# GPS_Sheet.net
KiCad netlist of a schematic drawn in Altium Designer
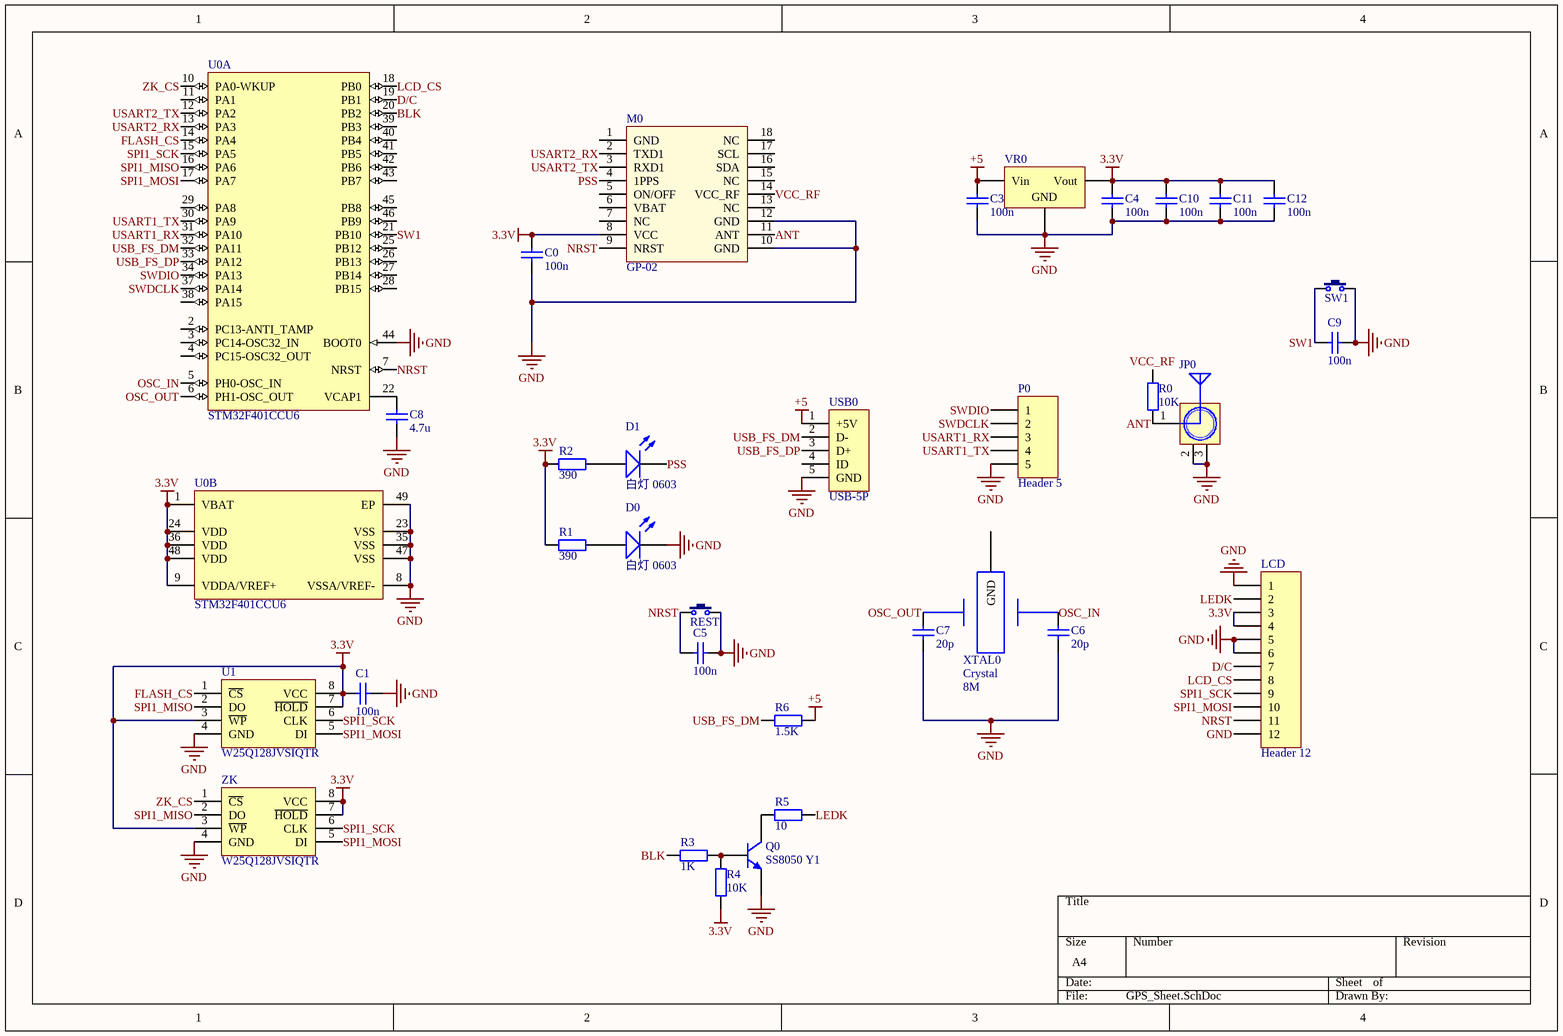
[diagram p0: GPS_Sheet.SchDoc]

(export (version "E")
  (design (tool "Eeschema 10.0.6"))
  (components
    (comp (ref "C0")
      (value "100n")
      (footprint "0805_C")
      (description "贴片电容")
      (libsource (lib "Miscellaneous Devices LC") (part "0805 100nF(104) 10% 50V"))
    )
    (comp (ref "C1")
      (value "100n")
      (footprint "0805_C")
      (description "贴片电容")
      (libsource (lib "Miscellaneous Devices LC") (part "0805 100nF(104) 10% 50V"))
    )
    (comp (ref "C3")
      (value "100n")
      (footprint "0805_C")
      (description "贴片电容")
      (libsource (lib "Miscellaneous Devices LC") (part "0805 100nF(104) 10% 50V"))
    )
    (comp (ref "C4")
      (value "100n")
      (footprint "0805_C")
      (description "贴片电容")
      (libsource (lib "Miscellaneous Devices LC") (part "0805 100nF(104) 10% 50V"))
    )
    (comp (ref "C5")
      (value "100n")
      (footprint "0805_C")
      (description "贴片电容")
      (libsource (lib "Miscellaneous Devices LC") (part "0805 100nF(104) 10% 50V"))
    )
    (comp (ref "C6")
      (value "20p")
      (footprint "0805_C")
      (description "贴片电容")
      (libsource (lib "Miscellaneous Devices LC") (part "0805 20pF (200) 5% 50V"))
    )
    (comp (ref "C7")
      (value "20p")
      (footprint "0805_C")
      (description "贴片电容")
      (libsource (lib "Miscellaneous Devices LC") (part "0805 20pF (200) 5% 50V"))
    )
    (comp (ref "C8")
      (value "4.7u")
      (footprint "0805_C")
      (description "贴片电容")
      (libsource (lib "Miscellaneous Devices LC") (part "0805 4.7uF (475) 10% 25V"))
    )
    (comp (ref "C9")
      (value "100n")
      (footprint "0805_C")
      (description "贴片电容")
      (libsource (lib "Miscellaneous Devices LC") (part "0805 100nF(104) 10% 50V"))
    )
    (comp (ref "C10")
      (value "100n")
      (footprint "0805_C")
      (description "贴片电容")
      (libsource (lib "Miscellaneous Devices LC") (part "0805 100nF(104) 10% 50V"))
    )
    (comp (ref "C11")
      (value "100n")
      (footprint "0805_C")
      (description "贴片电容")
      (libsource (lib "Miscellaneous Devices LC") (part "0805 100nF(104) 10% 50V"))
    )
    (comp (ref "C12")
      (value "100n")
      (footprint "0805_C")
      (description "贴片电容")
      (libsource (lib "Miscellaneous Devices LC") (part "0805 100nF(104) 10% 50V"))
    )
    (comp (ref "D0")
      (value "白灯 0603")
      (footprint "0603_LED_S1")
      (description "发光二极管")
      (libsource (lib "Miscellaneous Devices LC") (part "0603 白灯"))
    )
    (comp (ref "D1")
      (value "白灯 0603")
      (footprint "0603_LED_S1")
      (description "发光二极管")
      (libsource (lib "Miscellaneous Devices LC") (part "0603 白灯"))
    )
    (comp (ref "JP0")
      (value "SMA")
      (footprint "IPX")
      (description "SMA-2.4G射频天线接口")
      (fields (field (name "版权归属") "源创客"))
      (libsource (lib "接口类") (part "SMA"))
    )
    (comp (ref "LCD")
      (value "Header 12")
      (footprint "1.3_inch_LCD")
      (description "Header, 12-Pin")
      (fields (field (name "PUBLISHER") "Altium Limited"))
      (libsource (lib "Miscellaneous Connectors") (part "Header 12"))
    )
    (comp (ref "M0") (value "GP-02") (footprint "GP-02") (libsource (lib "GP-02 SCHLIB") (part "GP-02")))
    (comp (ref "P0")
      (value "Header 5")
      (footprint "HDR1X5")
      (description "Header, 5-Pin")
      (fields (field (name "PUBLISHER") "Altium Limited"))
      (libsource (lib "Miscellaneous Connectors") (part "Header 5"))
    )
    (comp (ref "Q0")
      (value "SS8050 Y1")
      (footprint "SOT-23(SOT-23-3)")
      (description "三极管")
      (libsource (lib "Miscellaneous Devices LC") (part "SOT-23 SS8050 Y1"))
    )
    (comp (ref "R0")
      (value "10K")
      (footprint "0805_R")
      (description "贴片电阻")
      (libsource (lib "Miscellaneous Devices LC") (part "0805 10KΩ (1002) 1%"))
    )
    (comp (ref "R1")
      (value "390")
      (footprint "0805_R")
      (description "贴片电阻")
      (libsource (lib "Miscellaneous Devices LC") (part "0805 390Ω (3900) 1%"))
    )
    (comp (ref "R2")
      (value "390")
      (footprint "0805_R")
      (description "贴片电阻")
      (libsource (lib "Miscellaneous Devices LC") (part "0805 390Ω (3900) 1%"))
    )
    (comp (ref "R3")
      (value "1K")
      (footprint "0805_R")
      (description "贴片电阻")
      (libsource (lib "Miscellaneous Devices LC") (part "0805 1KΩ (1001) 1%"))
    )
    (comp (ref "R4")
      (value "10K")
      (footprint "0805_R")
      (description "贴片电阻")
      (libsource (lib "Miscellaneous Devices LC") (part "0805 10KΩ (1002) 1%"))
    )
    (comp (ref "R5")
      (value "10")
      (footprint "0805_R")
      (description "贴片电阻")
      (libsource (lib "Miscellaneous Devices LC") (part "0805 10Ω (10R0) 1%"))
    )
    (comp (ref "R6")
      (value "1.5K")
      (footprint "0805_R")
      (description "贴片电阻")
      (libsource (lib "Miscellaneous Devices LC") (part "0805 1.5KΩ (1501) 1%"))
    )
    (comp (ref "REST")
      (value "3x6x5")
      (footprint "TSW SMD-3*6*2.5")
      (description "3x6轻触开关")
      (fields (field (name "版权归属") "源创客"))
      (libsource (lib "按键-开关") (part "TSW 3x6"))
    )
    (comp (ref "SW1")
      (value "3x6x5")
      (footprint "TSW SMD-3*6*2.5")
      (description "3x6轻触开关")
      (fields (field (name "版权归属") "源创客"))
      (libsource (lib "按键-开关") (part "TSW 3x6"))
    )
    (comp (ref "U0")
      (value "STM32F401CCU6")
      (footprint "STM-UFQFPN48_N")
      (fields (field (name "MANUFACTURER") "STMicroelectronics"))
      (libsource (lib "STMicroelectronics STM32 F4") (part "STM32F401CCU6"))
    )
    (comp (ref "U1")
      (value "W25Q128JVSIQTR")
      (footprint "SOIC-8_208mil")
      (description "Flash ROM")
      (libsource (lib "Miscellaneous Devices LC") (part "W25Q128JVSIQTR_[C97521]"))
    )
    (comp (ref "USB0")
      (value "USB-5P")
      (footprint "USB-MICRO_B")
      (description "微型USB母座")
      (fields (field (name "版权归属") "源创客"))
      (libsource (lib "接口类") (part "USB-5P"))
    )
    (comp (ref "VR0")
      (value "AMS1117-3.3")
      (footprint "SOT-223")
      (description "低压差线性稳压(LDO)")
      (libsource (lib "Miscellaneous Devices LC") (part "SOT-223 AMS1117-3.3"))
    )
    (comp (ref "XTAL0")
      (value "Crystal")
      (footprint "XTAL_DIP")
      (description "Crystal without source")
      (fields (field (name "FREQUENCE") "8M"))
      (libsource (lib "SmallJu_Lib") (part "XTAL"))
    )
    (comp (ref "ZK")
      (value "W25Q128JVSIQTR")
      (footprint "SOIC-8_208mil")
      (description "Flash ROM")
      (libsource (lib "Miscellaneous Devices LC") (part "W25Q128JVSIQTR_[C97521]"))
    )
  )
  (nets
    (net (code "1") (name "+5") (class "Default")
      (node (ref "C3") (pin "2") (pinfunction "2_2") (pintype "passive"))
      (node (ref "R6") (pin "2") (pinfunction "2_2") (pintype "passive"))
      (node (ref "USB0") (pin "1") (pinfunction "+5V_1") (pintype "passive"))
      (node (ref "VR0") (pin "3") (pinfunction "Vin_3") (pintype "passive"))
    )
    (net (code "2") (name "/ANT") (class "Default")
      (node (ref "JP0") (pin "1") (pinfunction "ANT_1") (pintype "passive"))
      (node (ref "M0") (pin "11") (pinfunction "ANT_11") (pintype "passive"))
      (node (ref "R0") (pin "1") (pinfunction "1_1") (pintype "passive"))
    )
    (net (code "3") (name "/BLK") (class "Default")
      (node (ref "R3") (pin "2") (pinfunction "2_2") (pintype "passive"))
      (node (ref "U0") (pin "20") (pinfunction "PB2_20") (pintype "bidirectional"))
    )
    (net (code "4") (name "/D{slash}C") (class "Default")
      (node (ref "LCD") (pin "7") (pinfunction "7_7") (pintype "passive"))
      (node (ref "U0") (pin "19") (pinfunction "PB1_19") (pintype "bidirectional"))
    )
    (net (code "5") (name "/FLASH_CS") (class "Default")
      (node (ref "U0") (pin "14") (pinfunction "PA4_14") (pintype "bidirectional"))
      (node (ref "U1") (pin "1") (pinfunction "~{CS}_1") (pintype "passive"))
    )
    (net (code "6") (name "/LCD_CS") (class "Default")
      (node (ref "LCD") (pin "8") (pinfunction "8_8") (pintype "passive"))
      (node (ref "U0") (pin "18") (pinfunction "PB0_18") (pintype "bidirectional"))
    )
    (net (code "7") (name "/LEDK") (class "Default")
      (node (ref "LCD") (pin "2") (pinfunction "2_2") (pintype "passive"))
      (node (ref "R5") (pin "2") (pinfunction "2_2") (pintype "passive"))
    )
    (net (code "8") (name "/NRST") (class "Default")
      (node (ref "C5") (pin "1") (pinfunction "1_1") (pintype "passive"))
      (node (ref "LCD") (pin "11") (pinfunction "11_11") (pintype "passive"))
      (node (ref "M0") (pin "9") (pinfunction "NRST_9") (pintype "passive"))
      (node (ref "REST") (pin "1") (pinfunction "1_1") (pintype "passive"))
      (node (ref "U0") (pin "7") (pinfunction "NRST_7") (pintype "bidirectional"))
    )
    (net (code "9") (name "/OSC_IN") (class "Default")
      (node (ref "C6") (pin "2") (pinfunction "2_2") (pintype "passive"))
      (node (ref "U0") (pin "5") (pinfunction "PH0-OSC_IN_5") (pintype "bidirectional"))
      (node (ref "XTAL0") (pin "1") (pintype "passive"))
    )
    (net (code "10") (name "/OSC_OUT") (class "Default")
      (node (ref "C7") (pin "2") (pinfunction "2_2") (pintype "passive"))
      (node (ref "U0") (pin "6") (pinfunction "PH1-OSC_OUT_6") (pintype "bidirectional"))
      (node (ref "XTAL0") (pin "2") (pintype "passive"))
    )
    (net (code "11") (name "/PSS") (class "Default")
      (node (ref "D1") (pin "K") (pinfunction "K_K") (pintype "passive"))
      (node (ref "M0") (pin "4") (pinfunction "1PPS_4") (pintype "passive"))
    )
    (net (code "12") (name "/SPI1_MISO") (class "Default")
      (node (ref "U0") (pin "16") (pinfunction "PA6_16") (pintype "bidirectional"))
      (node (ref "U1") (pin "2") (pinfunction "DO_2") (pintype "passive"))
      (node (ref "ZK") (pin "2") (pinfunction "DO_2") (pintype "passive"))
    )
    (net (code "13") (name "/SPI1_MOSI") (class "Default")
      (node (ref "LCD") (pin "10") (pinfunction "10_10") (pintype "passive"))
      (node (ref "U0") (pin "17") (pinfunction "PA7_17") (pintype "bidirectional"))
      (node (ref "U1") (pin "5") (pinfunction "DI_5") (pintype "passive"))
      (node (ref "ZK") (pin "5") (pinfunction "DI_5") (pintype "passive"))
    )
    (net (code "14") (name "/SPI1_SCK") (class "Default")
      (node (ref "LCD") (pin "9") (pinfunction "9_9") (pintype "passive"))
      (node (ref "U0") (pin "15") (pinfunction "PA5_15") (pintype "bidirectional"))
      (node (ref "U1") (pin "6") (pinfunction "CLK_6") (pintype "passive"))
      (node (ref "ZK") (pin "6") (pinfunction "CLK_6") (pintype "passive"))
    )
    (net (code "15") (name "/SW1") (class "Default")
      (node (ref "C9") (pin "1") (pinfunction "1_1") (pintype "passive"))
      (node (ref "SW1") (pin "1") (pinfunction "1_1") (pintype "passive"))
      (node (ref "U0") (pin "21") (pinfunction "PB10_21") (pintype "bidirectional"))
    )
    (net (code "16") (name "/SWDCLK") (class "Default")
      (node (ref "P0") (pin "2") (pinfunction "2_2") (pintype "passive"))
      (node (ref "U0") (pin "37") (pinfunction "PA14_37") (pintype "bidirectional"))
    )
    (net (code "17") (name "/SWDIO") (class "Default")
      (node (ref "P0") (pin "1") (pinfunction "1_1") (pintype "passive"))
      (node (ref "U0") (pin "34") (pinfunction "PA13_34") (pintype "bidirectional"))
    )
    (net (code "18") (name "/USART1_RX") (class "Default")
      (node (ref "P0") (pin "3") (pinfunction "3_3") (pintype "passive"))
      (node (ref "U0") (pin "31") (pinfunction "PA10_31") (pintype "bidirectional"))
    )
    (net (code "19") (name "/USART1_TX") (class "Default")
      (node (ref "P0") (pin "4") (pinfunction "4_4") (pintype "passive"))
      (node (ref "U0") (pin "30") (pinfunction "PA9_30") (pintype "bidirectional"))
    )
    (net (code "20") (name "/USART2_RX") (class "Default")
      (node (ref "M0") (pin "2") (pinfunction "TXD1_2") (pintype "passive"))
      (node (ref "U0") (pin "13") (pinfunction "PA3_13") (pintype "bidirectional"))
    )
    (net (code "21") (name "/USART2_TX") (class "Default")
      (node (ref "M0") (pin "3") (pinfunction "RXD1_3") (pintype "passive"))
      (node (ref "U0") (pin "12") (pinfunction "PA2_12") (pintype "bidirectional"))
    )
    (net (code "22") (name "/USB_FS_DM") (class "Default")
      (node (ref "R6") (pin "1") (pinfunction "1_1") (pintype "passive"))
      (node (ref "U0") (pin "32") (pinfunction "PA11_32") (pintype "bidirectional"))
      (node (ref "USB0") (pin "2") (pinfunction "D-_2") (pintype "passive"))
    )
    (net (code "23") (name "/USB_FS_DP") (class "Default")
      (node (ref "U0") (pin "33") (pinfunction "PA12_33") (pintype "bidirectional"))
      (node (ref "USB0") (pin "3") (pinfunction "D+_3") (pintype "passive"))
    )
    (net (code "24") (name "/VCC_RF") (class "Default")
      (node (ref "M0") (pin "14") (pinfunction "VCC_RF_14") (pintype "passive"))
      (node (ref "R0") (pin "2") (pinfunction "2_2") (pintype "passive"))
    )
    (net (code "25") (name "/ZK_CS") (class "Default")
      (node (ref "U0") (pin "10") (pinfunction "PA0-WKUP_10") (pintype "bidirectional"))
      (node (ref "ZK") (pin "1") (pinfunction "~{CS}_1") (pintype "passive"))
    )
    (net (code "26") (name "3.3V") (class "Default")
      (node (ref "C0") (pin "2") (pinfunction "2_2") (pintype "passive"))
      (node (ref "C1") (pin "2") (pinfunction "2_2") (pintype "passive"))
      (node (ref "C10") (pin "2") (pinfunction "2_2") (pintype "passive"))
      (node (ref "C11") (pin "2") (pinfunction "2_2") (pintype "passive"))
      (node (ref "C12") (pin "2") (pinfunction "2_2") (pintype "passive"))
      (node (ref "C4") (pin "2") (pinfunction "2_2") (pintype "passive"))
      (node (ref "LCD") (pin "3") (pinfunction "3_3") (pintype "passive"))
      (node (ref "LCD") (pin "4") (pinfunction "4_4") (pintype "passive"))
      (node (ref "M0") (pin "8") (pinfunction "VCC_8") (pintype "passive"))
      (node (ref "R1") (pin "1") (pinfunction "1_1") (pintype "passive"))
      (node (ref "R2") (pin "1") (pinfunction "1_1") (pintype "passive"))
      (node (ref "R4") (pin "1") (pinfunction "1_1") (pintype "passive"))
      (node (ref "U0") (pin "1") (pinfunction "VBAT_1") (pintype "power_in"))
      (node (ref "U0") (pin "24") (pinfunction "VDD_24") (pintype "power_in"))
      (node (ref "U0") (pin "36") (pinfunction "VDD_36") (pintype "power_in"))
      (node (ref "U0") (pin "48") (pinfunction "VDD_48") (pintype "power_in"))
      (node (ref "U0") (pin "9") (pinfunction "VDDA/VREF+_9") (pintype "power_in"))
      (node (ref "U1") (pin "3") (pinfunction "~{WP}_3") (pintype "passive"))
      (node (ref "U1") (pin "7") (pinfunction "~{HOLD}_7") (pintype "passive"))
      (node (ref "U1") (pin "8") (pinfunction "VCC_8") (pintype "passive"))
      (node (ref "VR0") (pin "2") (pinfunction "Vout_2") (pintype "passive"))
      (node (ref "ZK") (pin "3") (pinfunction "~{WP}_3") (pintype "passive"))
      (node (ref "ZK") (pin "7") (pinfunction "~{HOLD}_7") (pintype "passive"))
      (node (ref "ZK") (pin "8") (pinfunction "VCC_8") (pintype "passive"))
    )
    (net (code "27") (name "GND") (class "Default")
      (node (ref "C0") (pin "1") (pinfunction "1_1") (pintype "passive"))
      (node (ref "C1") (pin "1") (pinfunction "1_1") (pintype "passive"))
      (node (ref "C10") (pin "1") (pinfunction "1_1") (pintype "passive"))
      (node (ref "C11") (pin "1") (pinfunction "1_1") (pintype "passive"))
      (node (ref "C12") (pin "1") (pinfunction "1_1") (pintype "passive"))
      (node (ref "C3") (pin "1") (pinfunction "1_1") (pintype "passive"))
      (node (ref "C4") (pin "1") (pinfunction "1_1") (pintype "passive"))
      (node (ref "C5") (pin "2") (pinfunction "2_2") (pintype "passive"))
      (node (ref "C6") (pin "1") (pinfunction "1_1") (pintype "passive"))
      (node (ref "C7") (pin "1") (pinfunction "1_1") (pintype "passive"))
      (node (ref "C8") (pin "1") (pinfunction "1_1") (pintype "passive"))
      (node (ref "C9") (pin "2") (pinfunction "2_2") (pintype "passive"))
      (node (ref "D0") (pin "K") (pinfunction "K_K") (pintype "passive"))
      (node (ref "JP0") (pin "2") (pinfunction "GND_2") (pintype "passive"))
      (node (ref "JP0") (pin "3") (pinfunction "GND_3") (pintype "passive"))
      (node (ref "LCD") (pin "1") (pinfunction "1_1") (pintype "passive"))
      (node (ref "LCD") (pin "12") (pinfunction "12_12") (pintype "passive"))
      (node (ref "LCD") (pin "5") (pinfunction "5_5") (pintype "passive"))
      (node (ref "LCD") (pin "6") (pinfunction "6_6") (pintype "passive"))
      (node (ref "M0") (pin "10") (pinfunction "GND_10") (pintype "passive"))
      (node (ref "M0") (pin "12") (pinfunction "GND_12") (pintype "passive"))
      (node (ref "P0") (pin "5") (pinfunction "5_5") (pintype "passive"))
      (node (ref "Q0") (pin "2") (pinfunction "E_2") (pintype "passive"))
      (node (ref "REST") (pin "2") (pinfunction "2_2") (pintype "passive"))
      (node (ref "SW1") (pin "2") (pinfunction "2_2") (pintype "passive"))
      (node (ref "U0") (pin "23") (pinfunction "VSS_23") (pintype "power_in"))
      (node (ref "U0") (pin "35") (pinfunction "VSS_35") (pintype "power_in"))
      (node (ref "U0") (pin "44") (pinfunction "BOOT0_44") (pintype "input"))
      (node (ref "U0") (pin "47") (pinfunction "VSS_47") (pintype "power_in"))
      (node (ref "U0") (pin "49") (pinfunction "EP_49") (pintype "power_in"))
      (node (ref "U0") (pin "8") (pinfunction "VSSA/VREF-_8") (pintype "power_in"))
      (node (ref "U1") (pin "4") (pinfunction "GND_4") (pintype "passive"))
      (node (ref "USB0") (pin "5") (pinfunction "GND_5") (pintype "passive"))
      (node (ref "VR0") (pin "1") (pinfunction "GND_1") (pintype "passive"))
      (node (ref "ZK") (pin "4") (pinfunction "GND_4") (pintype "passive"))
    )
    (net (code "28") (name "Net-(D0-PadA)") (class "Default")
      (node (ref "D0") (pin "A") (pinfunction "A_A") (pintype "passive"))
      (node (ref "R1") (pin "2") (pinfunction "2_2") (pintype "passive"))
    )
    (net (code "29") (name "Net-(D1-PadA)") (class "Default")
      (node (ref "D1") (pin "A") (pinfunction "A_A") (pintype "passive"))
      (node (ref "R2") (pin "2") (pinfunction "2_2") (pintype "passive"))
    )
    (net (code "30") (name "Net-(Q0-B)") (class "Default")
      (node (ref "Q0") (pin "1") (pinfunction "B_1") (pintype "passive"))
      (node (ref "R3") (pin "1") (pinfunction "1_1") (pintype "passive"))
      (node (ref "R4") (pin "2") (pinfunction "2_2") (pintype "passive"))
    )
    (net (code "31") (name "Net-(Q0-C)") (class "Default")
      (node (ref "Q0") (pin "3") (pinfunction "C_3") (pintype "passive"))
      (node (ref "R5") (pin "1") (pinfunction "1_1") (pintype "passive"))
    )
    (net (code "32") (name "Net-(U0A-VCAP1)") (class "Default")
      (node (ref "C8") (pin "2") (pinfunction "2_2") (pintype "passive"))
      (node (ref "U0") (pin "22") (pinfunction "VCAP1_22") (pintype "power_in"))
    )
    (net (code "33") (name "unconnected-(M0-GND-Pad1)") (class "Default")
      (node (ref "M0") (pin "1") (pinfunction "GND_1") (pintype "passive"))
    )
    (net (code "34") (name "unconnected-(M0-NC-Pad7)") (class "Default")
      (node (ref "M0") (pin "7") (pinfunction "NC_7") (pintype "passive"))
    )
    (net (code "35") (name "unconnected-(M0-NC-Pad13)") (class "Default")
      (node (ref "M0") (pin "13") (pinfunction "NC_13") (pintype "passive"))
    )
    (net (code "36") (name "unconnected-(M0-NC-Pad15)") (class "Default")
      (node (ref "M0") (pin "15") (pinfunction "NC_15") (pintype "passive"))
    )
    (net (code "37") (name "unconnected-(M0-NC-Pad18)") (class "Default")
      (node (ref "M0") (pin "18") (pinfunction "NC_18") (pintype "passive"))
    )
    (net (code "38") (name "unconnected-(M0-ON{slash}OFF-Pad5)") (class "Default")
      (node (ref "M0") (pin "5") (pinfunction "ON/OFF_5") (pintype "passive"))
    )
    (net (code "39") (name "unconnected-(M0-SCL-Pad17)") (class "Default")
      (node (ref "M0") (pin "17") (pinfunction "SCL_17") (pintype "passive"))
    )
    (net (code "40") (name "unconnected-(M0-SDA-Pad16)") (class "Default")
      (node (ref "M0") (pin "16") (pinfunction "SDA_16") (pintype "passive"))
    )
    (net (code "41") (name "unconnected-(M0-VBAT-Pad6)") (class "Default")
      (node (ref "M0") (pin "6") (pinfunction "VBAT_6") (pintype "passive"))
    )
    (net (code "42") (name "unconnected-(U0A-PA1-Pad11)") (class "Default")
      (node (ref "U0") (pin "11") (pinfunction "PA1_11") (pintype "bidirectional"))
    )
    (net (code "43") (name "unconnected-(U0A-PA8-Pad29)") (class "Default")
      (node (ref "U0") (pin "29") (pinfunction "PA8_29") (pintype "bidirectional"))
    )
    (net (code "44") (name "unconnected-(U0A-PA15-Pad38)") (class "Default")
      (node (ref "U0") (pin "38") (pinfunction "PA15_38") (pintype "bidirectional"))
    )
    (net (code "45") (name "unconnected-(U0A-PB3-Pad39)") (class "Default")
      (node (ref "U0") (pin "39") (pinfunction "PB3_39") (pintype "bidirectional"))
    )
    (net (code "46") (name "unconnected-(U0A-PB4-Pad40)") (class "Default")
      (node (ref "U0") (pin "40") (pinfunction "PB4_40") (pintype "bidirectional"))
    )
    (net (code "47") (name "unconnected-(U0A-PB5-Pad41)") (class "Default")
      (node (ref "U0") (pin "41") (pinfunction "PB5_41") (pintype "bidirectional"))
    )
    (net (code "48") (name "unconnected-(U0A-PB6-Pad42)") (class "Default")
      (node (ref "U0") (pin "42") (pinfunction "PB6_42") (pintype "bidirectional"))
    )
    (net (code "49") (name "unconnected-(U0A-PB7-Pad43)") (class "Default")
      (node (ref "U0") (pin "43") (pinfunction "PB7_43") (pintype "bidirectional"))
    )
    (net (code "50") (name "unconnected-(U0A-PB8-Pad45)") (class "Default")
      (node (ref "U0") (pin "45") (pinfunction "PB8_45") (pintype "bidirectional"))
    )
    (net (code "51") (name "unconnected-(U0A-PB9-Pad46)") (class "Default")
      (node (ref "U0") (pin "46") (pinfunction "PB9_46") (pintype "bidirectional"))
    )
    (net (code "52") (name "unconnected-(U0A-PB12-Pad25)") (class "Default")
      (node (ref "U0") (pin "25") (pinfunction "PB12_25") (pintype "bidirectional"))
    )
    (net (code "53") (name "unconnected-(U0A-PB13-Pad26)") (class "Default")
      (node (ref "U0") (pin "26") (pinfunction "PB13_26") (pintype "bidirectional"))
    )
    (net (code "54") (name "unconnected-(U0A-PB14-Pad27)") (class "Default")
      (node (ref "U0") (pin "27") (pinfunction "PB14_27") (pintype "bidirectional"))
    )
    (net (code "55") (name "unconnected-(U0A-PB15-Pad28)") (class "Default")
      (node (ref "U0") (pin "28") (pinfunction "PB15_28") (pintype "bidirectional"))
    )
    (net (code "56") (name "unconnected-(U0A-PC13-ANTI_TAMP-Pad2)") (class "Default")
      (node (ref "U0") (pin "2") (pinfunction "PC13-ANTI_TAMP_2") (pintype "bidirectional"))
    )
    (net (code "57") (name "unconnected-(U0A-PC14-OSC32_IN-Pad3)") (class "Default")
      (node (ref "U0") (pin "3") (pinfunction "PC14-OSC32_IN_3") (pintype "bidirectional"))
    )
    (net (code "58") (name "unconnected-(U0A-PC15-OSC32_OUT-Pad4)") (class "Default")
      (node (ref "U0") (pin "4") (pinfunction "PC15-OSC32_OUT_4") (pintype "bidirectional"))
    )
    (net (code "59") (name "unconnected-(USB0-ID-Pad4)") (class "Default")
      (node (ref "USB0") (pin "4") (pinfunction "ID_4") (pintype "passive"))
    )
    (net (code "60") (name "unconnected-(XTAL0-GND-Pad3)") (class "Default")
      (node (ref "XTAL0") (pin "3") (pinfunction "GND_3") (pintype "passive"))
    )
  )
)
